# LDO_Schematic.net
KiCad netlist of a schematic drawn in Altium Designer
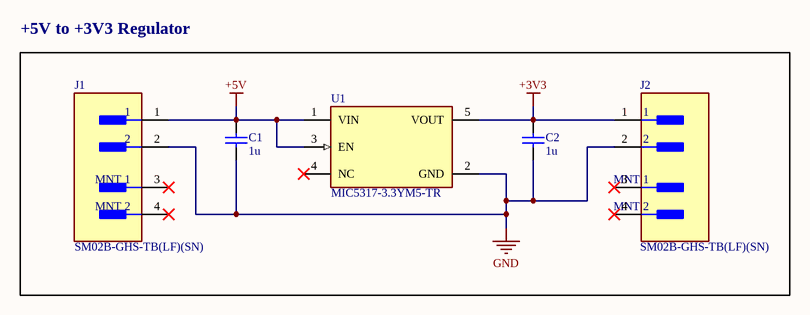
[diagram p0: LDO_Schematic.SchDoc]

(export (version "E")
  (design (tool "Eeschema 10.0.6"))
  (components
    (comp (ref "C1")
      (value "1u")
      (footprint "CAPC2013X145X50NL20T20")
      (fields (field (name "PART NUMBER") "VJ0805Y105KXQRW1BC") (field (name "MANUFACTURER") "Vitramon"))
      (libsource (lib "Altium Content Vault") (part "CAP"))
    )
    (comp (ref "C2")
      (value "1u")
      (footprint "CAPC2013X145X50NL20T20")
      (fields (field (name "PART NUMBER") "VJ0805Y105KXQRW1BC") (field (name "MANUFACTURER") "Vitramon"))
      (libsource (lib "Altium Content Vault") (part "CAP"))
    )
    (comp (ref "J1")
      (value "SM02B-GHS-TB(LF)(SN)")
      (footprint "FP-SM02B-GHS-TB_LF_SN-MFG")
      (description "CONN HEADER SMD R/A 2POS 1.25MM")
      (libsource (lib "Altium Content Vault") (part "56ec3178a87b3978bdc1b3682cd516a"))
    )
    (comp (ref "J2")
      (value "SM02B-GHS-TB(LF)(SN)")
      (footprint "FP-SM02B-GHS-TB_LF_SN-MFG")
      (description "CONN HEADER SMD R/A 2POS 1.25MM")
      (libsource (lib "") (part "56ec3178a87b3978bdc1b3682cd516a_1"))
    )
    (comp (ref "U1")
      (value "MIC5317-3.3YM5-TR")
      (footprint "FP-SOT23-5LD-PL-1-MFG")
      (description "IC REG LINEAR 3.3V 150MA SOT23-5")
      (libsource (lib "Altium Content Vault") (part "0a093dae7315cdc977fd108dde87457"))
    )
  )
  (nets
    (net (code "1") (name "+3V3") (class "Default")
      (node (ref "C2") (pin "2") (pinfunction "2_2") (pintype "passive"))
      (node (ref "J2") (pin "1") (pinfunction "1_1") (pintype "passive"))
      (node (ref "U1") (pin "5") (pinfunction "VOUT_5") (pintype "power_in"))
    )
    (net (code "2") (name "+5V") (class "Default")
      (node (ref "C1") (pin "2") (pinfunction "2_2") (pintype "passive"))
      (node (ref "J1") (pin "1") (pinfunction "1_1") (pintype "passive"))
      (node (ref "U1") (pin "1") (pinfunction "VIN_1") (pintype "power_in"))
      (node (ref "U1") (pin "3") (pinfunction "EN_3") (pintype "input"))
    )
    (net (code "3") (name "GND") (class "Default")
      (node (ref "C1") (pin "1") (pinfunction "1_1") (pintype "passive"))
      (node (ref "C2") (pin "1") (pinfunction "1_1") (pintype "passive"))
      (node (ref "J1") (pin "2") (pinfunction "2_2") (pintype "passive"))
      (node (ref "J2") (pin "2") (pinfunction "2_2") (pintype "passive"))
      (node (ref "U1") (pin "2") (pinfunction "GND_2") (pintype "power_in"))
    )
    (net (code "4") (name "unconnected-(J1-MNT_1-Pad3)") (class "Default")
      (node (ref "J1") (pin "3") (pinfunction "MNT_1_3") (pintype "passive+no_connect"))
    )
    (net (code "5") (name "unconnected-(J1-MNT_2-Pad4)") (class "Default")
      (node (ref "J1") (pin "4") (pinfunction "MNT_2_4") (pintype "passive+no_connect"))
    )
    (net (code "6") (name "unconnected-(J2-MNT_1-Pad3)") (class "Default")
      (node (ref "J2") (pin "3") (pinfunction "MNT_1_3") (pintype "passive+no_connect"))
    )
    (net (code "7") (name "unconnected-(J2-MNT_2-Pad4)") (class "Default")
      (node (ref "J2") (pin "4") (pinfunction "MNT_2_4") (pintype "passive+no_connect"))
    )
    (net (code "8") (name "unconnected-(U1-NC-Pad4)") (class "Default")
      (node (ref "U1") (pin "4") (pinfunction "NC_4") (pintype "passive+no_connect"))
    )
  )
)
